# Winston-BOTTOM.net
KiCad netlist of a schematic drawn in EAGLE
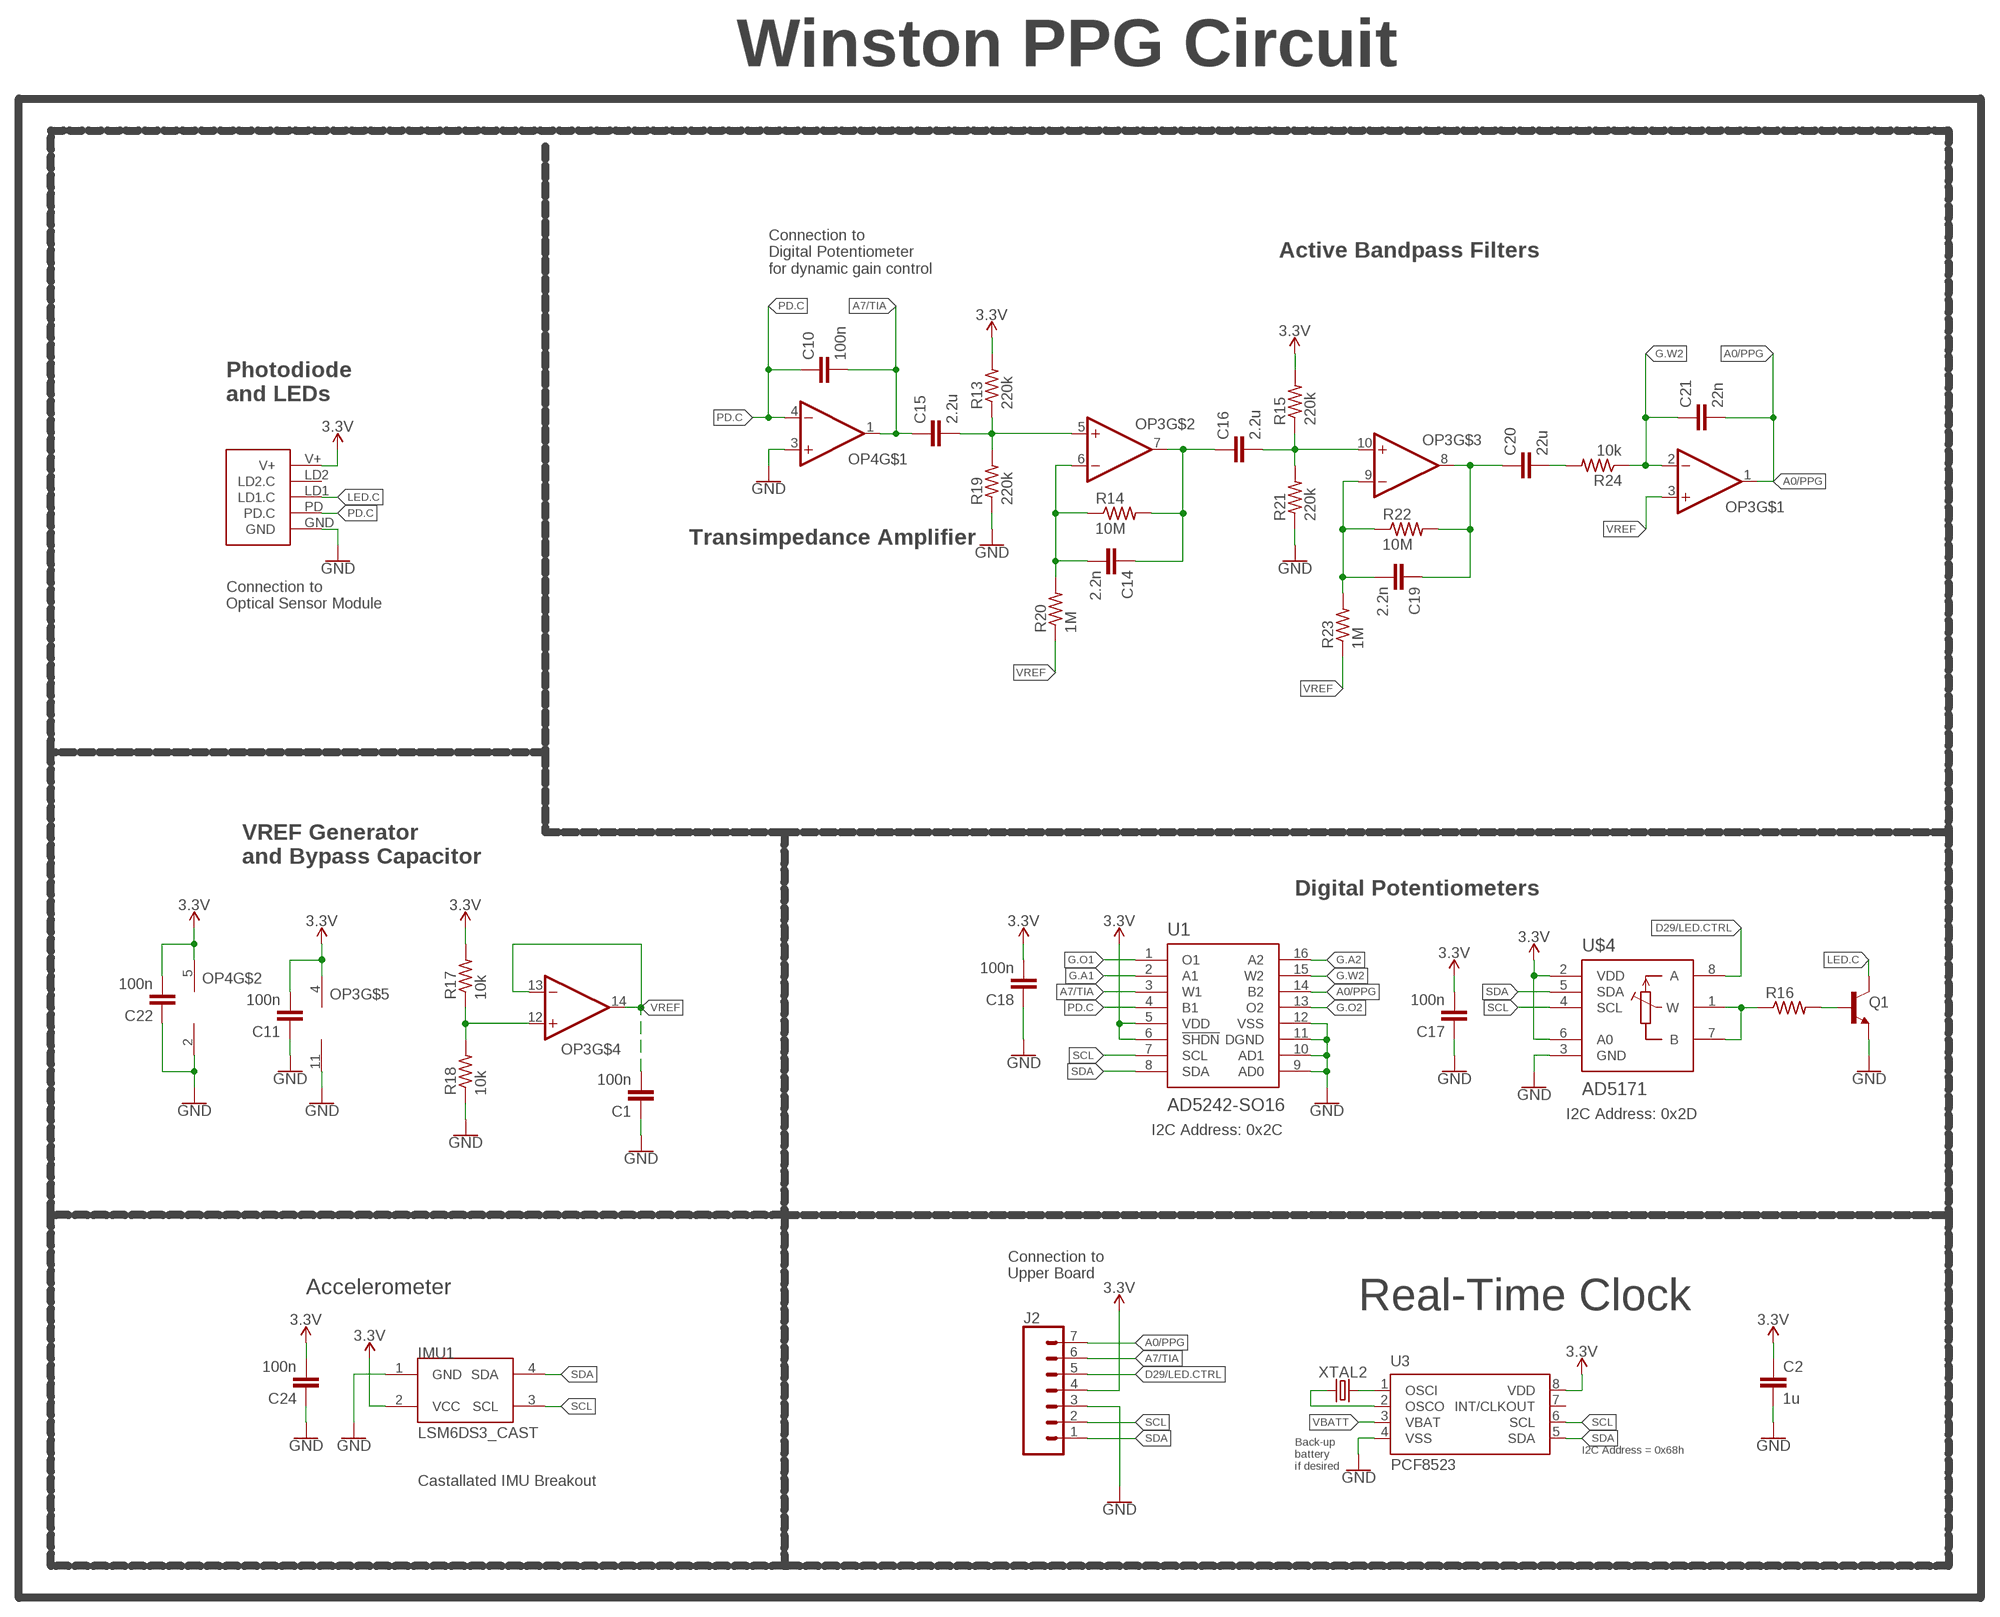
[diagram p0: schematic, sheet 1]

(export (version "E")
  (design (tool "Eeschema 10.0.6"))
  (components
    (comp (ref "C1")
      (value "100n")
      (footprint "eagle-import:C0603")
      (libsource (lib "eagle-import") (part "CAPACITOR0603"))
    )
    (comp (ref "C2")
      (value "1u")
      (footprint "eagle-import:C0603")
      (libsource (lib "eagle-import") (part "CAPACITOR0603"))
    )
    (comp (ref "C10")
      (value "100n")
      (footprint "eagle-import:C0603")
      (libsource (lib "eagle-import") (part "CAPACITOR0603"))
    )
    (comp (ref "C11")
      (value "100n")
      (footprint "eagle-import:C0603")
      (libsource (lib "eagle-import") (part "CAPACITOR0603"))
    )
    (comp (ref "C14")
      (value "2.2n")
      (footprint "eagle-import:C0603")
      (libsource (lib "eagle-import") (part "CAPACITOR0603"))
    )
    (comp (ref "C15")
      (value "2.2u")
      (footprint "eagle-import:C0603")
      (libsource (lib "eagle-import") (part "CAPACITOR0603"))
    )
    (comp (ref "C16")
      (value "2.2u")
      (footprint "eagle-import:C0603")
      (libsource (lib "eagle-import") (part "CAPACITOR0603"))
    )
    (comp (ref "C17")
      (value "100n")
      (footprint "eagle-import:C0603")
      (libsource (lib "eagle-import") (part "CAPACITOR0603"))
    )
    (comp (ref "C18")
      (value "100n")
      (footprint "eagle-import:C0603")
      (libsource (lib "eagle-import") (part "CAPACITOR0603"))
    )
    (comp (ref "C19")
      (value "2.2n")
      (footprint "eagle-import:C0603")
      (libsource (lib "eagle-import") (part "CAPACITOR0603"))
    )
    (comp (ref "C20")
      (value "22u")
      (footprint "eagle-import:C0603")
      (libsource (lib "eagle-import") (part "CAPACITOR0603"))
    )
    (comp (ref "C21")
      (value "22n")
      (footprint "eagle-import:C0603")
      (libsource (lib "eagle-import") (part "CAPACITOR0603"))
    )
    (comp (ref "C22")
      (value "100n")
      (footprint "eagle-import:C0603")
      (libsource (lib "eagle-import") (part "CAPACITOR0603"))
    )
    (comp (ref "C24")
      (value "100n")
      (footprint "eagle-import:C0603")
      (libsource (lib "eagle-import") (part "CAPACITOR0603"))
    )
    (comp (ref "IMU1")
      (value "LSM6DS3_CAST")
      (footprint "eagle-import:LSM6DS3_CAST")
      (libsource (lib "eagle-import") (part "LSM6DS3_CAST"))
    )
    (comp (ref "J2")
      (value "CONN_07-1.27MM")
      (footprint "eagle-import:1X07_1.27MM")
      (libsource (lib "eagle-import") (part "CONN_07-1.27MM"))
    )
    (comp (ref "OP3")
      (value "OP-QUAD-SO14")
      (footprint "eagle-import:SO14")
      (libsource (lib "eagle-import") (part "OP-QUAD-SO14"))
    )
    (comp (ref "OP4")
      (value "OP-SINGLEOT")
      (footprint "eagle-import:SOT23-5")
      (libsource (lib "eagle-import") (part "OP-SINGLEOT"))
    )
    (comp (ref "Q1")
      (value "NPN-GENERIC")
      (footprint "eagle-import:SOT23-3")
      (libsource (lib "eagle-import") (part "NPN-GENERIC"))
    )
    (comp (ref "R13")
      (value "220k")
      (footprint "eagle-import:R0603")
      (libsource (lib "eagle-import") (part "RESISTOR0603"))
    )
    (comp (ref "R14")
      (value "10M")
      (footprint "eagle-import:R0603")
      (libsource (lib "eagle-import") (part "RESISTOR0603"))
    )
    (comp (ref "R15")
      (value "220k")
      (footprint "eagle-import:R0603")
      (libsource (lib "eagle-import") (part "RESISTOR0603"))
    )
    (comp (ref "R16")
      (value "RESISTOR0603")
      (footprint "eagle-import:R0603")
      (libsource (lib "eagle-import") (part "RESISTOR0603"))
    )
    (comp (ref "R17")
      (value "10k")
      (footprint "eagle-import:R0402")
      (libsource (lib "eagle-import") (part "RESISTOR0402"))
    )
    (comp (ref "R18")
      (value "10k")
      (footprint "eagle-import:R0402")
      (libsource (lib "eagle-import") (part "RESISTOR0402"))
    )
    (comp (ref "R19")
      (value "220k")
      (footprint "eagle-import:R0603")
      (libsource (lib "eagle-import") (part "RESISTOR0603"))
    )
    (comp (ref "R20")
      (value "1M")
      (footprint "eagle-import:R0603")
      (libsource (lib "eagle-import") (part "RESISTOR0603"))
    )
    (comp (ref "R21")
      (value "220k")
      (footprint "eagle-import:R0603")
      (libsource (lib "eagle-import") (part "RESISTOR0603"))
    )
    (comp (ref "R22")
      (value "10M")
      (footprint "eagle-import:R0603")
      (libsource (lib "eagle-import") (part "RESISTOR0603"))
    )
    (comp (ref "R23")
      (value "1M")
      (footprint "eagle-import:R0603")
      (libsource (lib "eagle-import") (part "RESISTOR0603"))
    )
    (comp (ref "R24")
      (value "10k")
      (footprint "eagle-import:R0603")
      (libsource (lib "eagle-import") (part "RESISTOR0603"))
    )
    (comp (ref "U$3")
      (value "PPG.MODULE.2")
      (footprint "eagle-import:PPG.MODULE.2")
      (libsource (lib "eagle-import") (part "PPG.MODULE.2"))
    )
    (comp (ref "U$4")
      (value "AD5171")
      (footprint "eagle-import:SOT-23-8")
      (libsource (lib "eagle-import") (part "AD5171"))
    )
    (comp (ref "U1")
      (value "AD5242-SO16")
      (footprint "eagle-import:SO16")
      (libsource (lib "eagle-import") (part "AD5242-SO16"))
    )
    (comp (ref "U3")
      (value "PCF8523")
      (footprint "eagle-import:SO8")
      (libsource (lib "eagle-import") (part "PCF8523"))
    )
    (comp (ref "XTAL2")
      (value "32.7680kHz")
      (footprint "eagle-import:2-SMD.NOLEAD.2.0MMTO1.2MM")
      (fields (field (name "FREQ") "32.7680KHZ"))
      (libsource (lib "eagle-import") (part "CRYSTALECS-.327-12.5-12-C-TR"))
    )
  )
  (nets
    (net (code "1") (name "3.3V") (class "Default")
      (node (ref "C11") (pin "2") (pinfunction "2_2") (pintype "passive"))
      (node (ref "C17") (pin "2") (pinfunction "2_2") (pintype "passive"))
      (node (ref "C18") (pin "2") (pinfunction "2_2") (pintype "passive"))
      (node (ref "C2") (pin "1") (pinfunction "1_1") (pintype "passive"))
      (node (ref "C22") (pin "2") (pinfunction "2_2") (pintype "passive"))
      (node (ref "C24") (pin "2") (pinfunction "2_2") (pintype "passive"))
      (node (ref "IMU1") (pin "2") (pinfunction "VCC_2") (pintype "bidirectional"))
      (node (ref "J2") (pin "4") (pinfunction "4_4") (pintype "passive"))
      (node (ref "OP3") (pin "4") (pinfunction "V+_4") (pintype "power_in"))
      (node (ref "OP4") (pin "5") (pinfunction "V+_5") (pintype "power_in"))
      (node (ref "R13") (pin "2") (pinfunction "2_2") (pintype "passive"))
      (node (ref "R15") (pin "2") (pinfunction "2_2") (pintype "passive"))
      (node (ref "R17") (pin "2") (pinfunction "2_2") (pintype "passive"))
      (node (ref "U$3") (pin "V+") (pinfunction "V+_V+") (pintype "bidirectional"))
      (node (ref "U$4") (pin "2") (pinfunction "VDD_2") (pintype "bidirectional"))
      (node (ref "U$4") (pin "6") (pinfunction "A0_6") (pintype "bidirectional"))
      (node (ref "U1") (pin "5") (pinfunction "VDD_5") (pintype "bidirectional"))
      (node (ref "U1") (pin "6") (pinfunction "~{SHDN}_6") (pintype "bidirectional"))
      (node (ref "U3") (pin "8") (pinfunction "VDD_8") (pintype "power_in"))
    )
    (net (code "2") (name "A0{slash}PPG") (class "Default")
      (node (ref "C21") (pin "2") (pinfunction "2_2") (pintype "passive"))
      (node (ref "J2") (pin "7") (pinfunction "7_7") (pintype "passive"))
      (node (ref "OP3") (pin "1") (pinfunction "OUT_1") (pintype "output"))
      (node (ref "U1") (pin "14") (pinfunction "B2_14") (pintype "bidirectional"))
    )
    (net (code "3") (name "A7{slash}TIA") (class "Default")
      (node (ref "C10") (pin "2") (pinfunction "2_2") (pintype "passive"))
      (node (ref "C15") (pin "1") (pinfunction "1_1") (pintype "passive"))
      (node (ref "J2") (pin "6") (pinfunction "6_6") (pintype "passive"))
      (node (ref "OP4") (pin "1") (pinfunction "OUT_1") (pintype "output"))
      (node (ref "U1") (pin "3") (pinfunction "W1_3") (pintype "bidirectional"))
    )
    (net (code "4") (name "D29{slash}LED.CTRL") (class "Default")
      (node (ref "J2") (pin "5") (pinfunction "5_5") (pintype "passive"))
      (node (ref "U$4") (pin "8") (pinfunction "A_8") (pintype "bidirectional"))
    )
    (net (code "5") (name "G.A1") (class "Default")
      (node (ref "U1") (pin "2") (pinfunction "A1_2") (pintype "bidirectional"))
    )
    (net (code "6") (name "G.A2") (class "Default")
      (node (ref "U1") (pin "16") (pinfunction "A2_16") (pintype "bidirectional"))
    )
    (net (code "7") (name "G.O1") (class "Default")
      (node (ref "U1") (pin "1") (pinfunction "O1_1") (pintype "bidirectional"))
    )
    (net (code "8") (name "G.O2") (class "Default")
      (node (ref "U1") (pin "13") (pinfunction "O2_13") (pintype "bidirectional"))
    )
    (net (code "9") (name "G.W2") (class "Default")
      (node (ref "C21") (pin "1") (pinfunction "1_1") (pintype "passive"))
      (node (ref "OP3") (pin "2") (pinfunction "-IN_2") (pintype "input"))
      (node (ref "R24") (pin "1") (pinfunction "1_1") (pintype "passive"))
      (node (ref "U1") (pin "15") (pinfunction "W2_15") (pintype "bidirectional"))
    )
    (net (code "10") (name "GND") (class "Default")
      (node (ref "C1") (pin "1") (pinfunction "1_1") (pintype "passive"))
      (node (ref "C11") (pin "1") (pinfunction "1_1") (pintype "passive"))
      (node (ref "C17") (pin "1") (pinfunction "1_1") (pintype "passive"))
      (node (ref "C18") (pin "1") (pinfunction "1_1") (pintype "passive"))
      (node (ref "C2") (pin "2") (pinfunction "2_2") (pintype "passive"))
      (node (ref "C22") (pin "1") (pinfunction "1_1") (pintype "passive"))
      (node (ref "C24") (pin "1") (pinfunction "1_1") (pintype "passive"))
      (node (ref "IMU1") (pin "1") (pinfunction "GND_1") (pintype "bidirectional"))
      (node (ref "J2") (pin "3") (pinfunction "3_3") (pintype "passive"))
      (node (ref "OP3") (pin "11") (pinfunction "V-_11") (pintype "power_in"))
      (node (ref "OP4") (pin "2") (pinfunction "V-_2") (pintype "power_in"))
      (node (ref "OP4") (pin "3") (pinfunction "+IN_3") (pintype "input"))
      (node (ref "Q1") (pin "2") (pinfunction "E_2") (pintype "passive"))
      (node (ref "R18") (pin "1") (pinfunction "1_1") (pintype "passive"))
      (node (ref "R19") (pin "1") (pinfunction "1_1") (pintype "passive"))
      (node (ref "R21") (pin "1") (pinfunction "1_1") (pintype "passive"))
      (node (ref "U$3") (pin "GND") (pinfunction "GND_GND") (pintype "bidirectional"))
      (node (ref "U$4") (pin "3") (pinfunction "GND_3") (pintype "bidirectional"))
      (node (ref "U1") (pin "10") (pinfunction "AD1_10") (pintype "bidirectional"))
      (node (ref "U1") (pin "11") (pinfunction "DGND_11") (pintype "bidirectional"))
      (node (ref "U1") (pin "12") (pinfunction "VSS_12") (pintype "bidirectional"))
      (node (ref "U1") (pin "9") (pinfunction "AD0_9") (pintype "bidirectional"))
      (node (ref "U3") (pin "4") (pinfunction "VSS_4") (pintype "power_in"))
    )
    (net (code "11") (name "LED.C") (class "Default")
      (node (ref "Q1") (pin "3") (pinfunction "C_3") (pintype "passive"))
      (node (ref "U$3") (pin "LD1") (pinfunction "LD1.C_LD1") (pintype "bidirectional"))
    )
    (net (code "12") (name "Net-(C20-Pad2)") (class "Default")
      (node (ref "C20") (pin "2") (pinfunction "2_2") (pintype "passive"))
      (node (ref "R24") (pin "2") (pinfunction "2_2") (pintype "passive"))
    )
    (net (code "13") (name "Net-(OP3B-+IN)") (class "Default")
      (node (ref "C15") (pin "2") (pinfunction "2_2") (pintype "passive"))
      (node (ref "OP3") (pin "5") (pinfunction "+IN_5") (pintype "input"))
      (node (ref "R13") (pin "1") (pinfunction "1_1") (pintype "passive"))
      (node (ref "R19") (pin "2") (pinfunction "2_2") (pintype "passive"))
    )
    (net (code "14") (name "Net-(OP3B--IN)") (class "Default")
      (node (ref "C14") (pin "2") (pinfunction "2_2") (pintype "passive"))
      (node (ref "OP3") (pin "6") (pinfunction "-IN_6") (pintype "input"))
      (node (ref "R14") (pin "1") (pinfunction "1_1") (pintype "passive"))
      (node (ref "R20") (pin "2") (pinfunction "2_2") (pintype "passive"))
    )
    (net (code "15") (name "Net-(OP3B-OUT)") (class "Default")
      (node (ref "C14") (pin "1") (pinfunction "1_1") (pintype "passive"))
      (node (ref "C16") (pin "1") (pinfunction "1_1") (pintype "passive"))
      (node (ref "OP3") (pin "7") (pinfunction "OUT_7") (pintype "output"))
      (node (ref "R14") (pin "2") (pinfunction "2_2") (pintype "passive"))
    )
    (net (code "16") (name "Net-(OP3C-+IN)") (class "Default")
      (node (ref "C16") (pin "2") (pinfunction "2_2") (pintype "passive"))
      (node (ref "OP3") (pin "10") (pinfunction "+IN_10") (pintype "input"))
      (node (ref "R15") (pin "1") (pinfunction "1_1") (pintype "passive"))
      (node (ref "R21") (pin "2") (pinfunction "2_2") (pintype "passive"))
    )
    (net (code "17") (name "Net-(OP3C--IN)") (class "Default")
      (node (ref "C19") (pin "2") (pinfunction "2_2") (pintype "passive"))
      (node (ref "OP3") (pin "9") (pinfunction "-IN_9") (pintype "input"))
      (node (ref "R22") (pin "1") (pinfunction "1_1") (pintype "passive"))
      (node (ref "R23") (pin "2") (pinfunction "2_2") (pintype "passive"))
    )
    (net (code "18") (name "Net-(OP3C-OUT)") (class "Default")
      (node (ref "C19") (pin "1") (pinfunction "1_1") (pintype "passive"))
      (node (ref "C20") (pin "1") (pinfunction "1_1") (pintype "passive"))
      (node (ref "OP3") (pin "8") (pinfunction "OUT_8") (pintype "output"))
      (node (ref "R22") (pin "2") (pinfunction "2_2") (pintype "passive"))
    )
    (net (code "19") (name "Net-(OP3D-+IN)") (class "Default")
      (node (ref "OP3") (pin "12") (pinfunction "+IN_12") (pintype "input"))
      (node (ref "R17") (pin "1") (pinfunction "1_1") (pintype "passive"))
      (node (ref "R18") (pin "2") (pinfunction "2_2") (pintype "passive"))
    )
    (net (code "20") (name "Net-(Q1-B)") (class "Default")
      (node (ref "Q1") (pin "1") (pinfunction "B_1") (pintype "passive"))
      (node (ref "R16") (pin "2") (pinfunction "2_2") (pintype "passive"))
    )
    (net (code "21") (name "Net-(U$4-B)") (class "Default")
      (node (ref "R16") (pin "1") (pinfunction "1_1") (pintype "passive"))
      (node (ref "U$4") (pin "1") (pinfunction "W_1") (pintype "bidirectional"))
      (node (ref "U$4") (pin "7") (pinfunction "B_7") (pintype "bidirectional"))
    )
    (net (code "22") (name "Net-(U3-OSCI)") (class "Default")
      (node (ref "U3") (pin "1") (pinfunction "OSCI_1") (pintype "bidirectional"))
      (node (ref "XTAL2") (pin "P$2") (pinfunction "2_P$2") (pintype "passive"))
    )
    (net (code "23") (name "Net-(U3-OSCO)") (class "Default")
      (node (ref "U3") (pin "2") (pinfunction "OSCO_2") (pintype "bidirectional"))
      (node (ref "XTAL2") (pin "P$1") (pinfunction "1_P$1") (pintype "passive"))
    )
    (net (code "24") (name "PD.C") (class "Default")
      (node (ref "C10") (pin "1") (pinfunction "1_1") (pintype "passive"))
      (node (ref "OP4") (pin "4") (pinfunction "-IN_4") (pintype "input"))
      (node (ref "U$3") (pin "PD") (pinfunction "PD.C_PD") (pintype "bidirectional"))
      (node (ref "U1") (pin "4") (pinfunction "B1_4") (pintype "bidirectional"))
    )
    (net (code "25") (name "SCL") (class "Default")
      (node (ref "IMU1") (pin "3") (pinfunction "SCL_3") (pintype "bidirectional"))
      (node (ref "J2") (pin "2") (pinfunction "2_2") (pintype "passive"))
      (node (ref "U$4") (pin "4") (pinfunction "SCL_4") (pintype "bidirectional"))
      (node (ref "U1") (pin "7") (pinfunction "SCL_7") (pintype "bidirectional"))
      (node (ref "U3") (pin "6") (pinfunction "SCL_6") (pintype "bidirectional"))
    )
    (net (code "26") (name "SDA") (class "Default")
      (node (ref "IMU1") (pin "4") (pinfunction "SDA_4") (pintype "bidirectional"))
      (node (ref "J2") (pin "1") (pinfunction "1_1") (pintype "passive"))
      (node (ref "U$4") (pin "5") (pinfunction "SDA_5") (pintype "bidirectional"))
      (node (ref "U1") (pin "8") (pinfunction "SDA_8") (pintype "bidirectional"))
      (node (ref "U3") (pin "5") (pinfunction "SDA_5") (pintype "bidirectional"))
    )
    (net (code "27") (name "VBATT") (class "Default")
      (node (ref "U3") (pin "3") (pinfunction "VBAT_3") (pintype "power_in"))
    )
    (net (code "28") (name "VREF") (class "Default")
      (node (ref "C1") (pin "2") (pinfunction "2_2") (pintype "passive"))
      (node (ref "OP3") (pin "13") (pinfunction "-IN_13") (pintype "input"))
      (node (ref "OP3") (pin "14") (pinfunction "OUT_14") (pintype "output"))
      (node (ref "OP3") (pin "3") (pinfunction "+IN_3") (pintype "input"))
      (node (ref "R20") (pin "1") (pinfunction "1_1") (pintype "passive"))
      (node (ref "R23") (pin "1") (pinfunction "1_1") (pintype "passive"))
    )
    (net (code "29") (name "unconnected-(U$3-LD2.C-PadLD2)") (class "Default")
      (node (ref "U$3") (pin "LD2") (pinfunction "LD2.C_LD2") (pintype "bidirectional"))
    )
    (net (code "30") (name "unconnected-(U3-INT{slash}CLKOUT-Pad7)") (class "Default")
      (node (ref "U3") (pin "7") (pinfunction "INT/CLKOUT_7") (pintype "bidirectional"))
    )
  )
)
